# PTW_SENS.net
KiCad netlist of a schematic drawn in Altium Designer
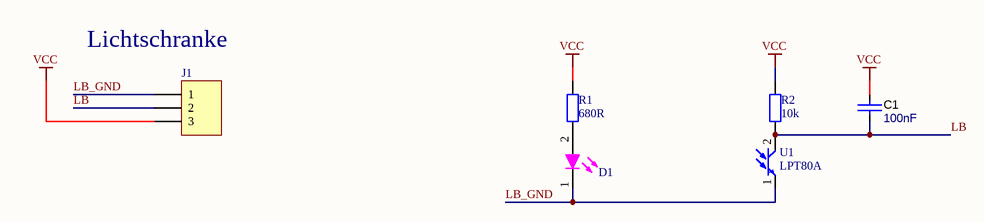
[diagram p0: PTW_SENS.SchDoc]

(export (version "E")
  (design (tool "Eeschema 10.0.6"))
  (components
    (comp (ref "C1")
      (value "100nF")
      (footprint "CAPC0402(1005)60_N")
      (description "Capacitor SMD Cer 0.47µF 10% 25V X5R 0402")
      (fields (field (name "TOLERANCE") "10%") (field (name "MANUFACTURER") "TDK"))
      (libsource (lib "CAPs") (part "CAPC_25V_X5R_0.47µF_0402"))
    )
    (comp (ref "D1")
      (value "IRL80A")
      (footprint "IRL80A")
      (description "GaAs Infrared Emitter")
      (libsource (lib "LEDs") (part "IRL80A"))
    )
    (comp (ref "J1")
      (value "Pin1x3")
      (footprint "HDR1X3")
      (description "Pinheader 1 Row 3Pins")
      (libsource (lib "Connector") (part "Pin1x3"))
    )
    (comp (ref "R1")
      (value "680R")
      (footprint "RESC0402(1005)_N")
      (description "R_0402")
      (fields (field (name "TOLERANCE") "±?%") (field (name "MANUFACTURER") "?"))
      (libsource (lib "RES") (part "RES_0402"))
    )
    (comp (ref "R2")
      (value "10k")
      (footprint "RESC0402(1005)_N")
      (description "R_0402")
      (fields (field (name "TOLERANCE") "±?%") (field (name "MANUFACTURER") "?"))
      (libsource (lib "RES") (part "RES_0402"))
    )
    (comp (ref "U1")
      (value "LPT80A")
      (footprint "LPT80A")
      (description "Silicon NPN Phototransistor")
      (libsource (lib "LEDs") (part "LPT80A"))
    )
  )
  (nets
    (net (code "1") (name "/LB") (class "Default")
      (node (ref "C1") (pin "2") (pintype "passive"))
      (node (ref "J1") (pin "2") (pinfunction "2_2") (pintype "passive"))
      (node (ref "R2") (pin "2") (pinfunction "2_2") (pintype "passive"))
      (node (ref "U1") (pin "2") (pinfunction "C_2") (pintype "passive"))
    )
    (net (code "2") (name "/LB_GND") (class "Default")
      (node (ref "D1") (pin "1") (pinfunction "K_1") (pintype "passive"))
      (node (ref "J1") (pin "1") (pinfunction "1_1") (pintype "passive"))
      (node (ref "U1") (pin "1") (pinfunction "E_1") (pintype "passive"))
    )
    (net (code "3") (name "Net-(D1-A)") (class "Default")
      (node (ref "D1") (pin "2") (pinfunction "A_2") (pintype "passive"))
      (node (ref "R1") (pin "2") (pinfunction "2_2") (pintype "passive"))
    )
    (net (code "4") (name "VCC") (class "Default")
      (node (ref "C1") (pin "1") (pintype "passive"))
      (node (ref "J1") (pin "3") (pinfunction "3_3") (pintype "passive"))
      (node (ref "R1") (pin "1") (pinfunction "1_1") (pintype "passive"))
      (node (ref "R2") (pin "1") (pinfunction "1_1") (pintype "passive"))
    )
  )
)
